# ProPrj_Ecoalerta_-_Esquema_tico_1_2026-0.net
KiCad netlist of a schematic drawn in EasyEDA Pro
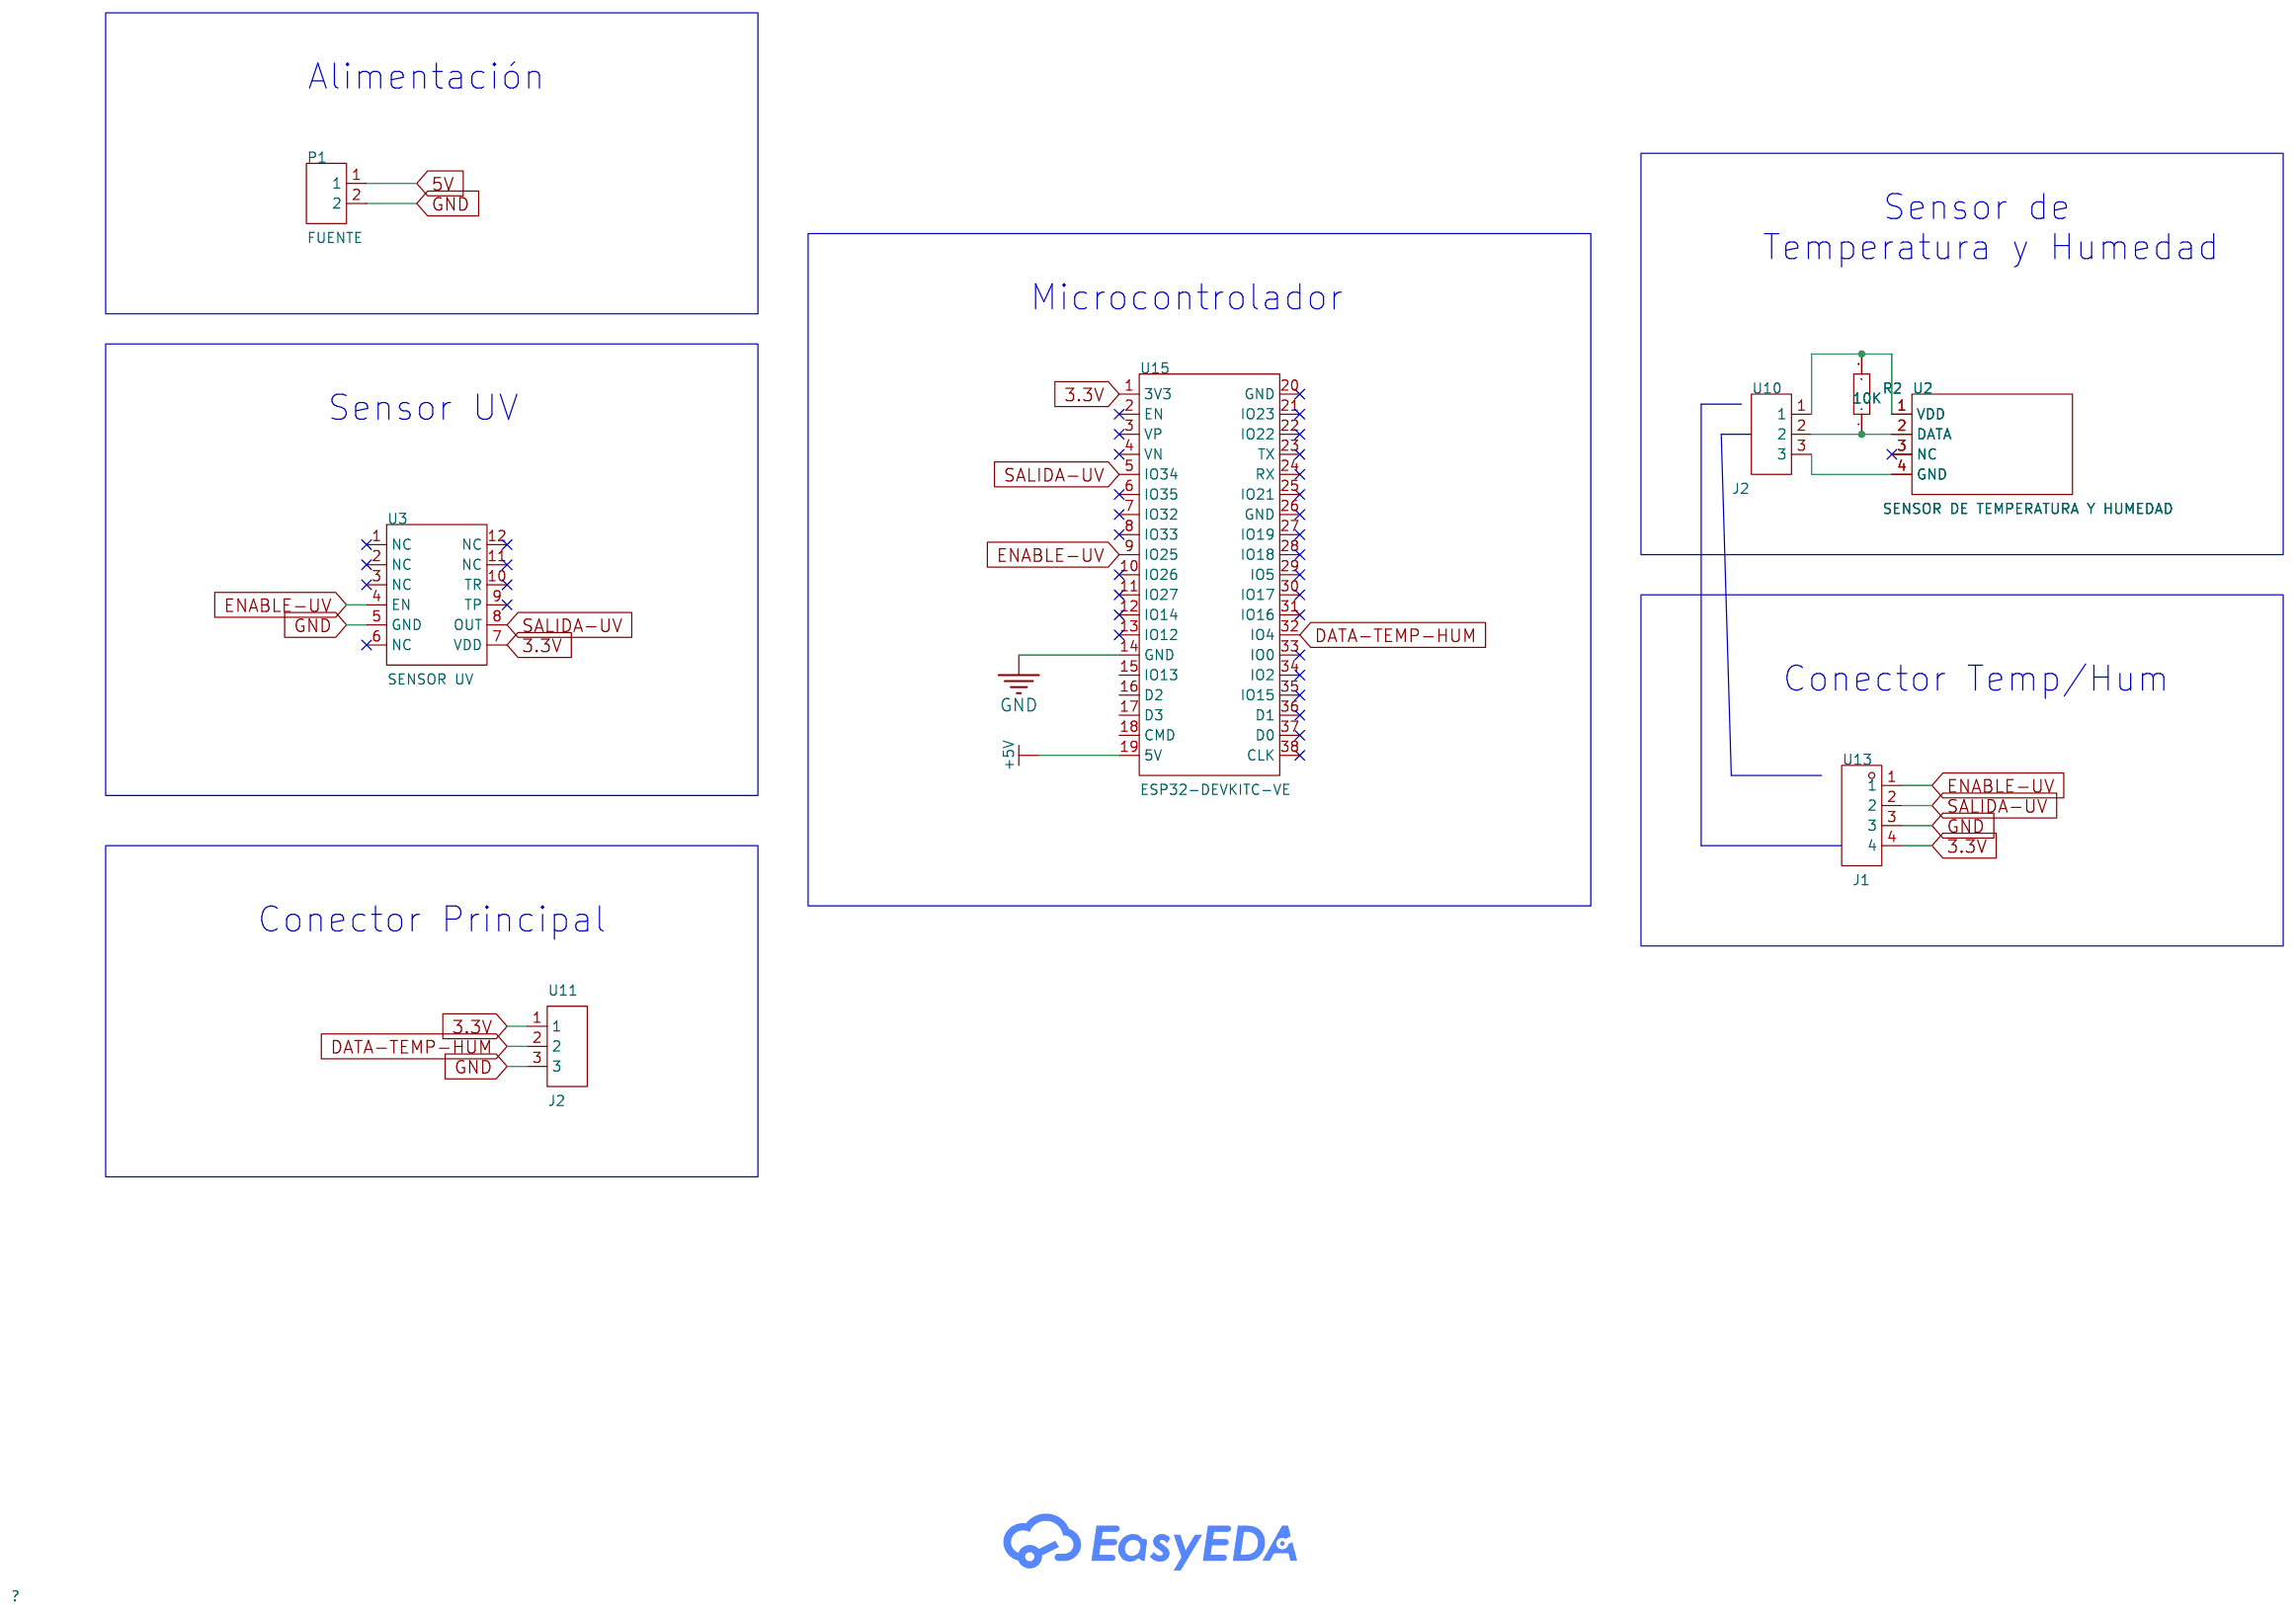
[diagram p0: schematic sheet]

(export (version "E")
  (design (tool "Eeschema 10.0.6"))
  (components
    (comp (ref "P1")
      (value "FUENTE")
      (footprint "easyedapro:CONN-TH_XY301V-A-5.0-2P")
      (libsource (lib "easyedapro") (part "KF301-2P接线端子"))
    )
    (comp (ref "R2") (value "10K") (footprint "easyedapro:R0603") (libsource (lib "easyedapro") (part "Res")))
    (comp (ref "U2")
      (value "SENSOR DE TEMPERATURA Y HUMEDAD")
      (footprint "easyedapro:SENSOR-TH_DHT11")
      (fields (field (name "Manufacturer") "广州奥松"))
      (libsource (lib "easyedapro") (part "DHT11"))
    )
    (comp (ref "U3")
      (value "SENSOR UV")
      (footprint "easyedapro:DFN-12_L4.0-W3.7-P1.00-BL")
      (fields (field (name "Manufacturer") "ROHM(罗姆)"))
      (libsource (lib "easyedapro") (part "ML8511-00FCZ05B"))
    )
    (comp (ref "U10")
      (value "J2")
      (footprint "easyedapro:CONN-TH_3P-P5.08_2EDG-5.08-3AW")
      (libsource (lib "easyedapro") (part "TERMINAL BLOCK KF2EDGK-5.08MM 3PIN"))
    )
    (comp (ref "U11")
      (value "J2")
      (footprint "easyedapro:CONN-TH_3P-P5.08_2EDG-5.08-3AW")
      (libsource (lib "easyedapro") (part "TERMINAL BLOCK KF2EDGK-5.08MM 3PIN"))
    )
    (comp (ref "U13")
      (value "J1")
      (footprint "easyedapro:TH-4P_L11.7-W9.3_C9900032758")
      (libsource (lib "easyedapro") (part "PE_GND_TERMINAL"))
    )
    (comp (ref "U15")
      (value "ESP32-DEVKITC-VE")
      (footprint "easyedapro:BULETM-SMD_ESP32-DEVKITC")
      (fields (field (name "Manufacturer") "ESPRESSIF(乐鑫)"))
      (libsource (lib "easyedapro") (part "ESP32-DEVKITC-VE"))
    )
  )
  (nets
    (net (code "1") (name "+5V") (class "Default")
      (node (ref "U15") (pin "19") (pinfunction "5V_19") (pintype "unspecified"))
    )
    (net (code "2") (name "3.3V") (class "Default")
      (node (ref "U11") (pin "1") (pinfunction "1_1") (pintype "unspecified"))
      (node (ref "U13") (pin "4") (pinfunction "4_4") (pintype "unspecified"))
      (node (ref "U15") (pin "1") (pinfunction "3V3_1") (pintype "unspecified"))
      (node (ref "U3") (pin "7") (pinfunction "VDD_7") (pintype "unspecified"))
    )
    (net (code "3") (name "5V") (class "Default")
      (node (ref "P1") (pin "1") (pinfunction "1_1") (pintype "unspecified"))
    )
    (net (code "4") (name "DATA-TEMP-HUM") (class "Default")
      (node (ref "U11") (pin "2") (pinfunction "2_2") (pintype "unspecified"))
      (node (ref "U15") (pin "32") (pinfunction "IO4_32") (pintype "unspecified"))
    )
    (net (code "5") (name "ENABLE-UV") (class "Default")
      (node (ref "U13") (pin "1") (pinfunction "1_1") (pintype "unspecified"))
      (node (ref "U15") (pin "9") (pinfunction "IO25_9") (pintype "unspecified"))
      (node (ref "U3") (pin "4") (pinfunction "EN_4") (pintype "unspecified"))
    )
    (net (code "6") (name "GND") (class "Default")
      (node (ref "P1") (pin "2") (pinfunction "2_2") (pintype "unspecified"))
      (node (ref "U11") (pin "3") (pinfunction "3_3") (pintype "unspecified"))
      (node (ref "U13") (pin "3") (pinfunction "3_3") (pintype "unspecified"))
      (node (ref "U15") (pin "14") (pinfunction "GND_14") (pintype "unspecified"))
      (node (ref "U3") (pin "5") (pinfunction "GND_5") (pintype "unspecified"))
    )
    (net (code "7") (name "Net-(U2-DATA)") (class "Default")
      (node (ref "R2") (pin "1") (pinfunction "1_1") (pintype "input"))
      (node (ref "U10") (pin "2") (pinfunction "2_2") (pintype "unspecified"))
      (node (ref "U2") (pin "2") (pinfunction "DATA_2") (pintype "unspecified"))
    )
    (net (code "8") (name "Net-(U2-GND)") (class "Default")
      (node (ref "U10") (pin "3") (pinfunction "3_3") (pintype "unspecified"))
      (node (ref "U2") (pin "4") (pinfunction "GND_4") (pintype "unspecified"))
    )
    (net (code "9") (name "Net-(U2-VDD)") (class "Default")
      (node (ref "R2") (pin "2") (pinfunction "2_2") (pintype "input"))
      (node (ref "U10") (pin "1") (pinfunction "1_1") (pintype "unspecified"))
      (node (ref "U2") (pin "1") (pinfunction "VDD_1") (pintype "unspecified"))
    )
    (net (code "10") (name "SALIDA-UV") (class "Default")
      (node (ref "U13") (pin "2") (pinfunction "2_2") (pintype "unspecified"))
      (node (ref "U15") (pin "5") (pinfunction "IO34_5") (pintype "unspecified"))
      (node (ref "U3") (pin "8") (pinfunction "OUT_8") (pintype "unspecified"))
    )
    (net (code "11") (name "unconnected-(U2-NC-Pad3)") (class "Default")
      (node (ref "U2") (pin "3") (pinfunction "NC_3") (pintype "unspecified+no_connect"))
    )
    (net (code "12") (name "unconnected-(U3-NC-Pad1)") (class "Default")
      (node (ref "U3") (pin "1") (pinfunction "NC_1") (pintype "unspecified+no_connect"))
    )
    (net (code "13") (name "unconnected-(U3-NC-Pad2)") (class "Default")
      (node (ref "U3") (pin "2") (pinfunction "NC_2") (pintype "unspecified+no_connect"))
    )
    (net (code "14") (name "unconnected-(U3-NC-Pad3)") (class "Default")
      (node (ref "U3") (pin "3") (pinfunction "NC_3") (pintype "unspecified+no_connect"))
    )
    (net (code "15") (name "unconnected-(U3-NC-Pad6)") (class "Default")
      (node (ref "U3") (pin "6") (pinfunction "NC_6") (pintype "unspecified+no_connect"))
    )
    (net (code "16") (name "unconnected-(U3-NC-Pad11)") (class "Default")
      (node (ref "U3") (pin "11") (pinfunction "NC_11") (pintype "unspecified+no_connect"))
    )
    (net (code "17") (name "unconnected-(U3-NC-Pad12)") (class "Default")
      (node (ref "U3") (pin "12") (pinfunction "NC_12") (pintype "unspecified+no_connect"))
    )
    (net (code "18") (name "unconnected-(U3-TP-Pad9)") (class "Default")
      (node (ref "U3") (pin "9") (pinfunction "TP_9") (pintype "unspecified+no_connect"))
    )
    (net (code "19") (name "unconnected-(U3-TR-Pad10)") (class "Default")
      (node (ref "U3") (pin "10") (pinfunction "TR_10") (pintype "unspecified+no_connect"))
    )
    (net (code "20") (name "unconnected-(U15-CLK-Pad38)") (class "Default")
      (node (ref "U15") (pin "38") (pinfunction "CLK_38") (pintype "unspecified+no_connect"))
    )
    (net (code "21") (name "unconnected-(U15-CMD-Pad18)") (class "Default")
      (node (ref "U15") (pin "18") (pinfunction "CMD_18") (pintype "unspecified"))
    )
    (net (code "22") (name "unconnected-(U15-D0-Pad37)") (class "Default")
      (node (ref "U15") (pin "37") (pinfunction "D0_37") (pintype "unspecified+no_connect"))
    )
    (net (code "23") (name "unconnected-(U15-D1-Pad36)") (class "Default")
      (node (ref "U15") (pin "36") (pinfunction "D1_36") (pintype "unspecified+no_connect"))
    )
    (net (code "24") (name "unconnected-(U15-D2-Pad16)") (class "Default")
      (node (ref "U15") (pin "16") (pinfunction "D2_16") (pintype "unspecified"))
    )
    (net (code "25") (name "unconnected-(U15-D3-Pad17)") (class "Default")
      (node (ref "U15") (pin "17") (pinfunction "D3_17") (pintype "unspecified"))
    )
    (net (code "26") (name "unconnected-(U15-EN-Pad2)") (class "Default")
      (node (ref "U15") (pin "2") (pinfunction "EN_2") (pintype "unspecified+no_connect"))
    )
    (net (code "27") (name "unconnected-(U15-GND-Pad20)") (class "Default")
      (node (ref "U15") (pin "20") (pinfunction "GND_20") (pintype "unspecified+no_connect"))
    )
    (net (code "28") (name "unconnected-(U15-GND-Pad26)") (class "Default")
      (node (ref "U15") (pin "26") (pinfunction "GND_26") (pintype "unspecified+no_connect"))
    )
    (net (code "29") (name "unconnected-(U15-IO0-Pad33)") (class "Default")
      (node (ref "U15") (pin "33") (pinfunction "IO0_33") (pintype "unspecified+no_connect"))
    )
    (net (code "30") (name "unconnected-(U15-IO2-Pad34)") (class "Default")
      (node (ref "U15") (pin "34") (pinfunction "IO2_34") (pintype "unspecified+no_connect"))
    )
    (net (code "31") (name "unconnected-(U15-IO5-Pad29)") (class "Default")
      (node (ref "U15") (pin "29") (pinfunction "IO5_29") (pintype "unspecified+no_connect"))
    )
    (net (code "32") (name "unconnected-(U15-IO12-Pad13)") (class "Default")
      (node (ref "U15") (pin "13") (pinfunction "IO12_13") (pintype "unspecified+no_connect"))
    )
    (net (code "33") (name "unconnected-(U15-IO13-Pad15)") (class "Default")
      (node (ref "U15") (pin "15") (pinfunction "IO13_15") (pintype "unspecified"))
    )
    (net (code "34") (name "unconnected-(U15-IO14-Pad12)") (class "Default")
      (node (ref "U15") (pin "12") (pinfunction "IO14_12") (pintype "unspecified+no_connect"))
    )
    (net (code "35") (name "unconnected-(U15-IO15-Pad35)") (class "Default")
      (node (ref "U15") (pin "35") (pinfunction "IO15_35") (pintype "unspecified+no_connect"))
    )
    (net (code "36") (name "unconnected-(U15-IO16-Pad31)") (class "Default")
      (node (ref "U15") (pin "31") (pinfunction "IO16_31") (pintype "unspecified+no_connect"))
    )
    (net (code "37") (name "unconnected-(U15-IO17-Pad30)") (class "Default")
      (node (ref "U15") (pin "30") (pinfunction "IO17_30") (pintype "unspecified+no_connect"))
    )
    (net (code "38") (name "unconnected-(U15-IO18-Pad28)") (class "Default")
      (node (ref "U15") (pin "28") (pinfunction "IO18_28") (pintype "unspecified+no_connect"))
    )
    (net (code "39") (name "unconnected-(U15-IO19-Pad27)") (class "Default")
      (node (ref "U15") (pin "27") (pinfunction "IO19_27") (pintype "unspecified+no_connect"))
    )
    (net (code "40") (name "unconnected-(U15-IO21-Pad25)") (class "Default")
      (node (ref "U15") (pin "25") (pinfunction "IO21_25") (pintype "unspecified+no_connect"))
    )
    (net (code "41") (name "unconnected-(U15-IO22-Pad22)") (class "Default")
      (node (ref "U15") (pin "22") (pinfunction "IO22_22") (pintype "unspecified+no_connect"))
    )
    (net (code "42") (name "unconnected-(U15-IO23-Pad21)") (class "Default")
      (node (ref "U15") (pin "21") (pinfunction "IO23_21") (pintype "unspecified+no_connect"))
    )
    (net (code "43") (name "unconnected-(U15-IO26-Pad10)") (class "Default")
      (node (ref "U15") (pin "10") (pinfunction "IO26_10") (pintype "unspecified+no_connect"))
    )
    (net (code "44") (name "unconnected-(U15-IO27-Pad11)") (class "Default")
      (node (ref "U15") (pin "11") (pinfunction "IO27_11") (pintype "unspecified+no_connect"))
    )
    (net (code "45") (name "unconnected-(U15-IO32-Pad7)") (class "Default")
      (node (ref "U15") (pin "7") (pinfunction "IO32_7") (pintype "unspecified+no_connect"))
    )
    (net (code "46") (name "unconnected-(U15-IO33-Pad8)") (class "Default")
      (node (ref "U15") (pin "8") (pinfunction "IO33_8") (pintype "unspecified+no_connect"))
    )
    (net (code "47") (name "unconnected-(U15-IO35-Pad6)") (class "Default")
      (node (ref "U15") (pin "6") (pinfunction "IO35_6") (pintype "unspecified+no_connect"))
    )
    (net (code "48") (name "unconnected-(U15-RX-Pad24)") (class "Default")
      (node (ref "U15") (pin "24") (pinfunction "RX_24") (pintype "unspecified+no_connect"))
    )
    (net (code "49") (name "unconnected-(U15-TX-Pad23)") (class "Default")
      (node (ref "U15") (pin "23") (pinfunction "TX_23") (pintype "unspecified+no_connect"))
    )
    (net (code "50") (name "unconnected-(U15-VN-Pad4)") (class "Default")
      (node (ref "U15") (pin "4") (pinfunction "VN_4") (pintype "unspecified+no_connect"))
    )
    (net (code "51") (name "unconnected-(U15-VP-Pad3)") (class "Default")
      (node (ref "U15") (pin "3") (pinfunction "VP_3") (pintype "unspecified+no_connect"))
    )
  )
)
